# line_follower.net
KiCad netlist of a schematic drawn in EAGLE
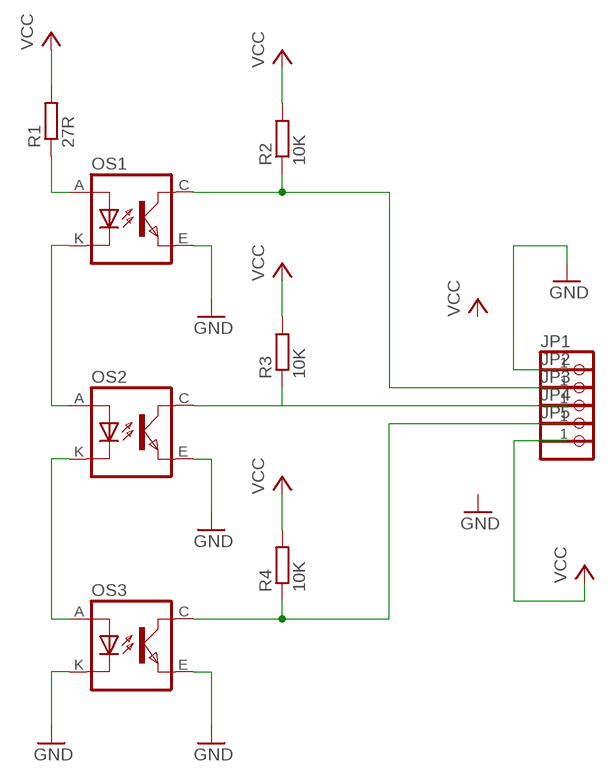
[diagram p0: schematic, sheet 1]

(export (version "E")
  (design (tool "Eeschema 10.0.6"))
  (components
    (comp (ref "JP1")
      (value "PINHD-1X1")
      (footprint "eagle-import:1X01")
      (libsource (lib "eagle-import") (part "PINHD-1X1"))
    )
    (comp (ref "JP2")
      (value "PINHD-1X1")
      (footprint "eagle-import:1X01")
      (libsource (lib "eagle-import") (part "PINHD-1X1"))
    )
    (comp (ref "JP3")
      (value "PINHD-1X1")
      (footprint "eagle-import:1X01")
      (libsource (lib "eagle-import") (part "PINHD-1X1"))
    )
    (comp (ref "JP4")
      (value "PINHD-1X1")
      (footprint "eagle-import:1X01")
      (libsource (lib "eagle-import") (part "PINHD-1X1"))
    )
    (comp (ref "JP5")
      (value "PINHD-1X1")
      (footprint "eagle-import:1X01")
      (libsource (lib "eagle-import") (part "PINHD-1X1"))
    )
    (comp (ref "OS1")
      (value "TCRT5000")
      (footprint "eagle-import:TCRT5000")
      (libsource (lib "eagle-import") (part "TCRT5000"))
    )
    (comp (ref "OS2")
      (value "TCRT5000")
      (footprint "eagle-import:TCRT5000")
      (libsource (lib "eagle-import") (part "TCRT5000"))
    )
    (comp (ref "OS3")
      (value "TCRT5000")
      (footprint "eagle-import:TCRT5000")
      (libsource (lib "eagle-import") (part "TCRT5000"))
    )
    (comp (ref "R1")
      (value "27R")
      (footprint "eagle-import:0204_7")
      (libsource (lib "eagle-import") (part "R-EU_0204/7"))
    )
    (comp (ref "R2")
      (value "10K")
      (footprint "eagle-import:0204_7")
      (libsource (lib "eagle-import") (part "R-EU_0204/7"))
    )
    (comp (ref "R3")
      (value "10K")
      (footprint "eagle-import:0204_7")
      (libsource (lib "eagle-import") (part "R-EU_0204/7"))
    )
    (comp (ref "R4")
      (value "10K")
      (footprint "eagle-import:0204_7")
      (libsource (lib "eagle-import") (part "R-EU_0204/7"))
    )
  )
  (nets
    (net (code "1") (name "GND") (class "Default")
      (node (ref "JP1") (pin "1") (pinfunction "1_1") (pintype "passive"))
      (node (ref "OS1") (pin "E") (pinfunction "EMITTER_E") (pintype "passive"))
      (node (ref "OS2") (pin "E") (pinfunction "EMITTER_E") (pintype "passive"))
      (node (ref "OS3") (pin "E") (pinfunction "EMITTER_E") (pintype "passive"))
      (node (ref "OS3") (pin "K") (pinfunction "CATHODE_K") (pintype "passive"))
    )
    (net (code "2") (name "Net-(OS1-ANODE)") (class "Default")
      (node (ref "OS1") (pin "A") (pinfunction "ANODE_A") (pintype "passive"))
      (node (ref "R1") (pin "1") (pinfunction "1_1") (pintype "passive"))
    )
    (net (code "3") (name "Net-(OS1-CATHODE)") (class "Default")
      (node (ref "OS1") (pin "K") (pinfunction "CATHODE_K") (pintype "passive"))
      (node (ref "OS2") (pin "A") (pinfunction "ANODE_A") (pintype "passive"))
    )
    (net (code "4") (name "Net-(OS1-COLLECTOR)") (class "Default")
      (node (ref "JP2") (pin "1") (pinfunction "1_1") (pintype "passive"))
      (node (ref "OS1") (pin "C") (pinfunction "COLLECTOR_C") (pintype "passive"))
      (node (ref "R2") (pin "1") (pinfunction "1_1") (pintype "passive"))
    )
    (net (code "5") (name "Net-(OS2-CATHODE)") (class "Default")
      (node (ref "OS2") (pin "K") (pinfunction "CATHODE_K") (pintype "passive"))
      (node (ref "OS3") (pin "A") (pinfunction "ANODE_A") (pintype "passive"))
    )
    (net (code "6") (name "Net-(OS2-COLLECTOR)") (class "Default")
      (node (ref "JP3") (pin "1") (pinfunction "1_1") (pintype "passive"))
      (node (ref "OS2") (pin "C") (pinfunction "COLLECTOR_C") (pintype "passive"))
      (node (ref "R3") (pin "1") (pinfunction "1_1") (pintype "passive"))
    )
    (net (code "7") (name "Net-(OS3-COLLECTOR)") (class "Default")
      (node (ref "JP4") (pin "1") (pinfunction "1_1") (pintype "passive"))
      (node (ref "OS3") (pin "C") (pinfunction "COLLECTOR_C") (pintype "passive"))
      (node (ref "R4") (pin "1") (pinfunction "1_1") (pintype "passive"))
    )
    (net (code "8") (name "VCC") (class "Default")
      (node (ref "JP5") (pin "1") (pinfunction "1_1") (pintype "passive"))
      (node (ref "R1") (pin "2") (pinfunction "2_2") (pintype "passive"))
      (node (ref "R2") (pin "2") (pinfunction "2_2") (pintype "passive"))
      (node (ref "R3") (pin "2") (pinfunction "2_2") (pintype "passive"))
      (node (ref "R4") (pin "2") (pinfunction "2_2") (pintype "passive"))
    )
  )
)
